# PWR2.net
KiCad netlist of a schematic drawn in Altium Designer
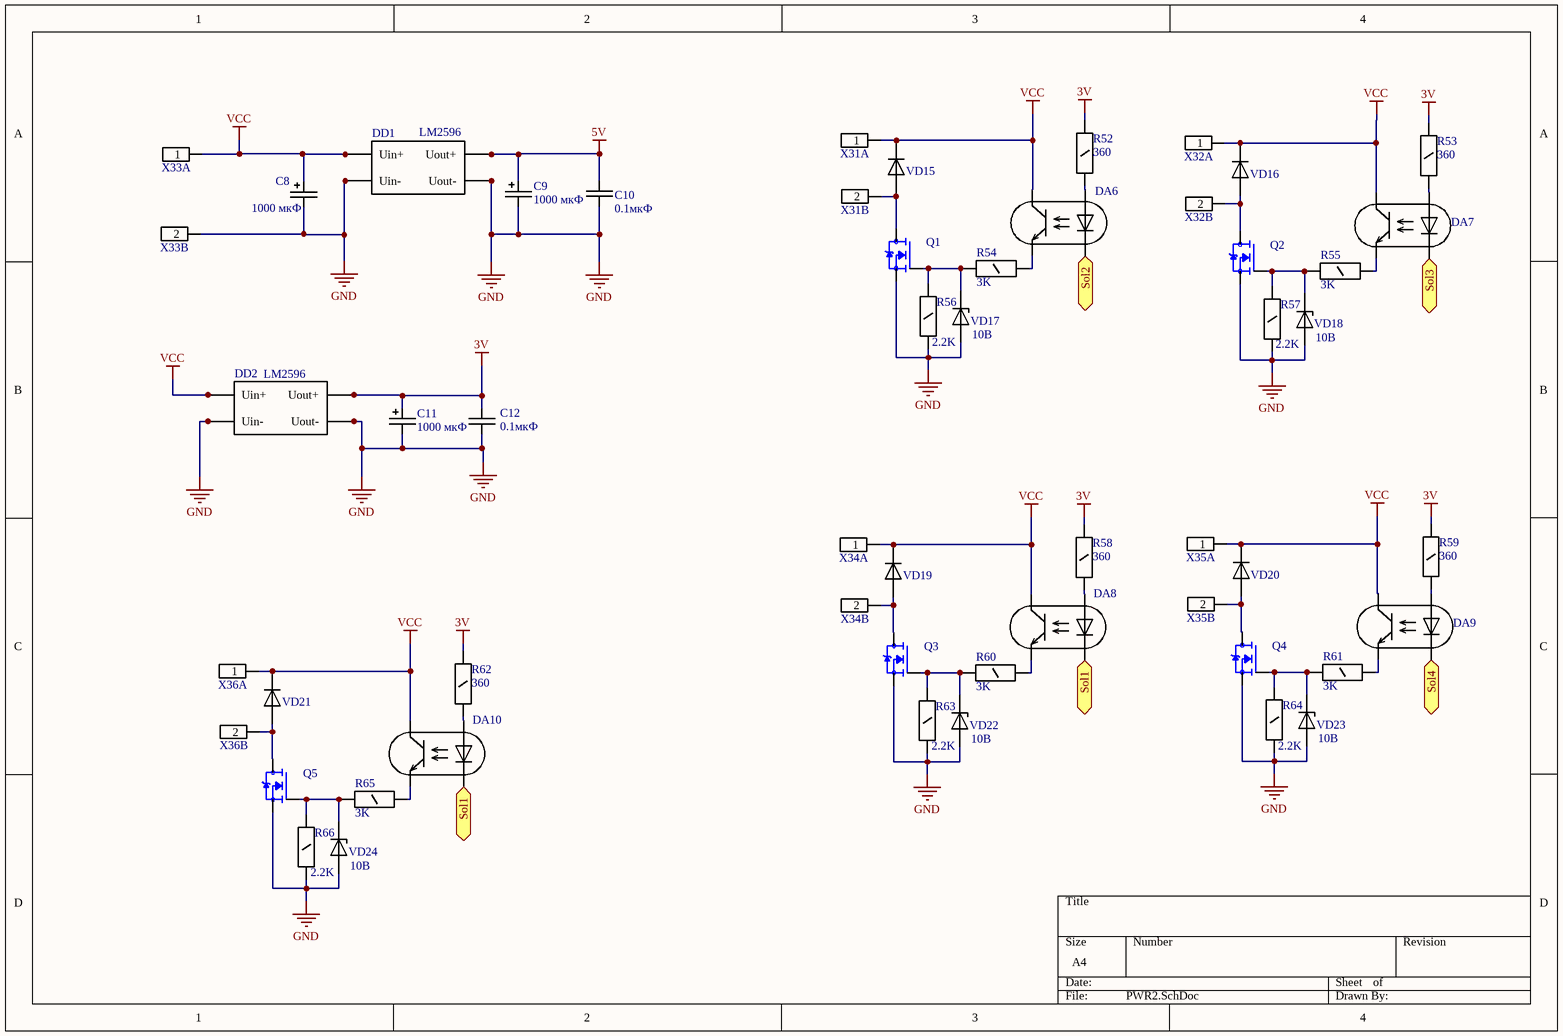
[diagram p0: PWR2.SchDoc]

(export (version "E")
  (design (tool "Eeschema 10.0.6"))
  (components
    (comp (ref "C8")
      (value "1000 мкФ")
      (footprint "C_10x5")
      (description "К50-35")
      (fields (field (name "TOLERANCE") "20%"))
      (libsource (lib "Res_end_Cap") (part "Конденсатор 25х12.5"))
    )
    (comp (ref "C9")
      (value "1000 мкФ")
      (footprint "C_10x5")
      (description "К50-35")
      (fields (field (name "TOLERANCE") "20%"))
      (libsource (lib "Res_end_Cap") (part "Конденсатор 25х12.5"))
    )
    (comp (ref "C10")
      (value "0.1мкФ")
      (footprint "C_1206")
      (description "SMD")
      (fields (field (name "VOLTAGE") "50B") (field (name "TOLERANCE") "10%"))
      (libsource (lib "Res_end_Cap") (part "Конденсатор 1210"))
    )
    (comp (ref "C11")
      (value "1000 мкФ")
      (footprint "C_10x5")
      (description "К50-35")
      (fields (field (name "TOLERANCE") "20%"))
      (libsource (lib "Res_end_Cap") (part "Конденсатор 25х12.5"))
    )
    (comp (ref "C12")
      (value "0.1мкФ")
      (footprint "C_1206")
      (description "SMD")
      (fields (field (name "VOLTAGE") "50B") (field (name "TOLERANCE") "10%"))
      (libsource (lib "Res_end_Cap") (part "Конденсатор 1210"))
    )
    (comp (ref "DA6")
      (value "KPC357NT0C")
      (footprint "Mini-flat-4")
      (description "оптрон, SMD")
      (libsource (lib "LEDendIND") (part "KPC357NT"))
    )
    (comp (ref "DA7")
      (value "KPC357NT0C")
      (footprint "Mini-flat-4")
      (description "оптрон, SMD")
      (libsource (lib "LEDendIND") (part "KPC357NT"))
    )
    (comp (ref "DA8")
      (value "KPC357NT0C")
      (footprint "Mini-flat-4")
      (description "оптрон, SMD")
      (libsource (lib "LEDendIND") (part "KPC357NT"))
    )
    (comp (ref "DA9")
      (value "KPC357NT0C")
      (footprint "Mini-flat-4")
      (description "оптрон, SMD")
      (libsource (lib "LEDendIND") (part "KPC357NT"))
    )
    (comp (ref "DA10")
      (value "KPC357NT0C")
      (footprint "Mini-flat-4")
      (description "оптрон, SMD")
      (libsource (lib "LEDendIND") (part "KPC357NT"))
    )
    (comp (ref "DD1")
      (value "LM2596")
      (footprint "LM2596")
      (description "Блок питания")
      (libsource (lib "MODULE") (part "LM2596"))
    )
    (comp (ref "DD2")
      (value "LM2596")
      (footprint "LM2596")
      (description "Блок питания")
      (libsource (lib "MODULE") (part "LM2596"))
    )
    (comp (ref "Q1")
      (value "IRFZ44N")
      (footprint "DPAK254P1524X483-3N:DPAK254P1524X483-3N")
      (description "N-Channel 55V 49A (Tc) 3.8W (Ta), 94W (Tc) Surface Mount D2PAK")
      (fields (field (name "MP") "IRFZ44NSTRRPBF") (field (name "MF") "Infineon Technologies"))
      (libsource (lib "Diod_transistor") (part "IRFZ44NSTRRPBF"))
    )
    (comp (ref "Q2")
      (value "IRFZ44N")
      (footprint "DPAK254P1524X483-3N:DPAK254P1524X483-3N")
      (description "N-Channel 55V 49A (Tc) 3.8W (Ta), 94W (Tc) Surface Mount D2PAK")
      (fields (field (name "MP") "IRFZ44NSTRRPBF") (field (name "MF") "Infineon Technologies"))
      (libsource (lib "Diod_transistor") (part "IRFZ44NSTRRPBF"))
    )
    (comp (ref "Q3")
      (value "IRFZ44N")
      (footprint "DPAK254P1524X483-3N:DPAK254P1524X483-3N")
      (description "N-Channel 55V 49A (Tc) 3.8W (Ta), 94W (Tc) Surface Mount D2PAK")
      (fields (field (name "MP") "IRFZ44NSTRRPBF") (field (name "MF") "Infineon Technologies"))
      (libsource (lib "Diod_transistor") (part "IRFZ44NSTRRPBF"))
    )
    (comp (ref "Q4")
      (value "IRFZ44N")
      (footprint "DPAK254P1524X483-3N:DPAK254P1524X483-3N")
      (description "N-Channel 55V 49A (Tc) 3.8W (Ta), 94W (Tc) Surface Mount D2PAK")
      (fields (field (name "MP") "IRFZ44NSTRRPBF") (field (name "MF") "Infineon Technologies"))
      (libsource (lib "Diod_transistor") (part "IRFZ44NSTRRPBF"))
    )
    (comp (ref "Q5")
      (value "IRFZ44N")
      (footprint "DPAK254P1524X483-3N:DPAK254P1524X483-3N")
      (description "N-Channel 55V 49A (Tc) 3.8W (Ta), 94W (Tc) Surface Mount D2PAK")
      (fields (field (name "MP") "IRFZ44NSTRRPBF") (field (name "MF") "Infineon Technologies"))
      (libsource (lib "Diod_transistor") (part "IRFZ44NSTRRPBF"))
    )
    (comp (ref "R52")
      (value "360")
      (footprint "R_1206")
      (description "0,25 Вт")
      (fields (field (name "POWER") "0.25 Вт") (field (name "TOLERANCE") "5%"))
      (libsource (lib "Res_end_Cap") (part "Резистор 1206"))
    )
    (comp (ref "R53")
      (value "360")
      (footprint "R_1206")
      (description "0,25 Вт")
      (fields (field (name "POWER") "0.25 Вт") (field (name "TOLERANCE") "5%"))
      (libsource (lib "Res_end_Cap") (part "Резистор 1206"))
    )
    (comp (ref "R54")
      (value "3K")
      (footprint "R_1206")
      (description "0,25 Вт")
      (fields (field (name "POWER") "0.25 Вт") (field (name "TOLERANCE") "5%"))
      (libsource (lib "") (part "Резистор 1206_2"))
    )
    (comp (ref "R55")
      (value "3K")
      (footprint "R_1206")
      (description "0,25 Вт")
      (fields (field (name "POWER") "0.25 Вт") (field (name "TOLERANCE") "5%"))
      (libsource (lib "") (part "Резистор 1206_2"))
    )
    (comp (ref "R56")
      (value "2.2K")
      (footprint "R_1206")
      (description "0,25 Вт")
      (fields (field (name "POWER") "0.25 Вт") (field (name "TOLERANCE") "5%"))
      (libsource (lib "") (part "Резистор 1206_1"))
    )
    (comp (ref "R57")
      (value "2.2K")
      (footprint "R_1206")
      (description "0,25 Вт")
      (fields (field (name "POWER") "0.25 Вт") (field (name "TOLERANCE") "5%"))
      (libsource (lib "") (part "Резистор 1206_1"))
    )
    (comp (ref "R58")
      (value "360")
      (footprint "R_1206")
      (description "0,25 Вт")
      (fields (field (name "POWER") "0.25 Вт") (field (name "TOLERANCE") "5%"))
      (libsource (lib "Res_end_Cap") (part "Резистор 1206"))
    )
    (comp (ref "R59")
      (value "360")
      (footprint "R_1206")
      (description "0,25 Вт")
      (fields (field (name "POWER") "0.25 Вт") (field (name "TOLERANCE") "5%"))
      (libsource (lib "Res_end_Cap") (part "Резистор 1206"))
    )
    (comp (ref "R60")
      (value "3K")
      (footprint "R_1206")
      (description "0,25 Вт")
      (fields (field (name "POWER") "0.25 Вт") (field (name "TOLERANCE") "5%"))
      (libsource (lib "") (part "Резистор 1206_2"))
    )
    (comp (ref "R61")
      (value "3K")
      (footprint "R_1206")
      (description "0,25 Вт")
      (fields (field (name "POWER") "0.25 Вт") (field (name "TOLERANCE") "5%"))
      (libsource (lib "") (part "Резистор 1206_2"))
    )
    (comp (ref "R62")
      (value "360")
      (footprint "R_1206")
      (description "0,25 Вт")
      (fields (field (name "POWER") "0.25 Вт") (field (name "TOLERANCE") "5%"))
      (libsource (lib "Res_end_Cap") (part "Резистор 1206"))
    )
    (comp (ref "R63")
      (value "2.2K")
      (footprint "R_1206")
      (description "0,25 Вт")
      (fields (field (name "POWER") "0.25 Вт") (field (name "TOLERANCE") "5%"))
      (libsource (lib "") (part "Резистор 1206_1"))
    )
    (comp (ref "R64")
      (value "2.2K")
      (footprint "R_1206")
      (description "0,25 Вт")
      (fields (field (name "POWER") "0.25 Вт") (field (name "TOLERANCE") "5%"))
      (libsource (lib "") (part "Резистор 1206_1"))
    )
    (comp (ref "R65")
      (value "3K")
      (footprint "R_1206")
      (description "0,25 Вт")
      (fields (field (name "POWER") "0.25 Вт") (field (name "TOLERANCE") "5%"))
      (libsource (lib "") (part "Резистор 1206_2"))
    )
    (comp (ref "R66")
      (value "2.2K")
      (footprint "R_1206")
      (description "0,25 Вт")
      (fields (field (name "POWER") "0.25 Вт") (field (name "TOLERANCE") "5%"))
      (libsource (lib "") (part "Резистор 1206_1"))
    )
    (comp (ref "VD15")
      (value "SMA400*")
      (footprint "SMA (DO-214AC)")
      (description "диод, SMD")
      (libsource (lib "Диоды и транзисторы") (part "SMA400*"))
    )
    (comp (ref "VD16")
      (value "SMA400*")
      (footprint "SMA (DO-214AC)")
      (description "диод, SMD")
      (libsource (lib "Диоды и транзисторы") (part "SMA400*"))
    )
    (comp (ref "VD17")
      (value "10В")
      (footprint "DL-35")
      (description "стабилитрон, SMD")
      (fields (field (name "POWER") "0.5 Вт"))
      (libsource (lib "Diod_transistor") (part "BZV55C***"))
    )
    (comp (ref "VD18")
      (value "10В")
      (footprint "DL-35")
      (description "стабилитрон, SMD")
      (fields (field (name "POWER") "0.5 Вт"))
      (libsource (lib "Diod_transistor") (part "BZV55C***"))
    )
    (comp (ref "VD19")
      (value "SMA400*")
      (footprint "SMA (DO-214AC)")
      (description "диод, SMD")
      (libsource (lib "Диоды и транзисторы") (part "SMA400*"))
    )
    (comp (ref "VD20")
      (value "SMA400*")
      (footprint "SMA (DO-214AC)")
      (description "диод, SMD")
      (libsource (lib "Диоды и транзисторы") (part "SMA400*"))
    )
    (comp (ref "VD21")
      (value "SMA400*")
      (footprint "SMA (DO-214AC)")
      (description "диод, SMD")
      (libsource (lib "Диоды и транзисторы") (part "SMA400*"))
    )
    (comp (ref "VD22")
      (value "10В")
      (footprint "DL-35")
      (description "стабилитрон, SMD")
      (fields (field (name "POWER") "0.5 Вт"))
      (libsource (lib "Diod_transistor") (part "BZV55C***"))
    )
    (comp (ref "VD23")
      (value "10В")
      (footprint "DL-35")
      (description "стабилитрон, SMD")
      (fields (field (name "POWER") "0.5 Вт"))
      (libsource (lib "Diod_transistor") (part "BZV55C***"))
    )
    (comp (ref "VD24")
      (value "10В")
      (footprint "DL-35")
      (description "стабилитрон, SMD")
      (fields (field (name "POWER") "0.5 Вт"))
      (libsource (lib "Diod_transistor") (part "BZV55C***"))
    )
    (comp (ref "X31")
      (value "DG508V-02")
      (footprint "DG508V-02")
      (description "клеммник винтовой 2к.,5.08мм")
      (libsource (lib "Klemniki") (part "DG508V-02"))
    )
    (comp (ref "X32")
      (value "DG508V-02")
      (footprint "DG508V-02")
      (description "клеммник винтовой 2к.,5.08мм")
      (libsource (lib "Klemniki") (part "DG508V-02"))
    )
    (comp (ref "X33")
      (value "DG508V-02")
      (footprint "DG508V-02")
      (description "клеммник винтовой 2к.,5.08мм")
      (libsource (lib "Klemniki") (part "DG508V-02"))
    )
    (comp (ref "X34")
      (value "DG508V-02")
      (footprint "DG508V-02")
      (description "клеммник винтовой 2к.,5.08мм")
      (libsource (lib "Klemniki") (part "DG508V-02"))
    )
    (comp (ref "X35")
      (value "DG508V-02")
      (footprint "DG508V-02")
      (description "клеммник винтовой 2к.,5.08мм")
      (libsource (lib "Klemniki") (part "DG508V-02"))
    )
    (comp (ref "X36")
      (value "DG508V-02")
      (footprint "DG508V-02")
      (description "клеммник винтовой 2к.,5.08мм")
      (libsource (lib "Klemniki") (part "DG508V-02"))
    )
  )
  (nets
    (net (code "1") (name "/Sol1") (class "Default")
      (node (ref "DA10") (pin "2") (pinfunction "2_2") (pintype "passive"))
      (node (ref "DA8") (pin "2") (pinfunction "2_2") (pintype "passive"))
    )
    (net (code "2") (name "/Sol2") (class "Default")
      (node (ref "DA6") (pin "2") (pinfunction "2_2") (pintype "passive"))
    )
    (net (code "3") (name "/Sol3") (class "Default")
      (node (ref "DA7") (pin "2") (pinfunction "2_2") (pintype "passive"))
    )
    (net (code "4") (name "/Sol4") (class "Default")
      (node (ref "DA9") (pin "2") (pinfunction "2_2") (pintype "passive"))
    )
    (net (code "5") (name "3V") (class "Default")
      (node (ref "C11") (pin "1") (pinfunction "1_1") (pintype "passive"))
      (node (ref "C12") (pin "1") (pinfunction "1_1") (pintype "passive"))
      (node (ref "DD2") (pin "5") (pinfunction "Uout+_5") (pintype "power_in"))
      (node (ref "DD2") (pin "6") (pinfunction "Uout+_6") (pintype "power_in"))
      (node (ref "R52") (pin "1") (pinfunction "1_1") (pintype "passive"))
      (node (ref "R53") (pin "1") (pinfunction "1_1") (pintype "passive"))
      (node (ref "R58") (pin "1") (pinfunction "1_1") (pintype "passive"))
      (node (ref "R59") (pin "1") (pinfunction "1_1") (pintype "passive"))
      (node (ref "R62") (pin "1") (pinfunction "1_1") (pintype "passive"))
    )
    (net (code "6") (name "5V") (class "Default")
      (node (ref "C10") (pin "1") (pinfunction "1_1") (pintype "passive"))
      (node (ref "C9") (pin "1") (pinfunction "1_1") (pintype "passive"))
      (node (ref "DD1") (pin "5") (pinfunction "Uout+_5") (pintype "power_in"))
      (node (ref "DD1") (pin "6") (pinfunction "Uout+_6") (pintype "power_in"))
    )
    (net (code "7") (name "GND") (class "Default")
      (node (ref "C10") (pin "2") (pinfunction "2_2") (pintype "passive"))
      (node (ref "C11") (pin "2") (pinfunction "2_2") (pintype "passive"))
      (node (ref "C12") (pin "2") (pinfunction "2_2") (pintype "passive"))
      (node (ref "C8") (pin "2") (pinfunction "2_2") (pintype "passive"))
      (node (ref "C9") (pin "2") (pinfunction "2_2") (pintype "passive"))
      (node (ref "DD1") (pin "3") (pinfunction "Uin-_3") (pintype "power_in"))
      (node (ref "DD1") (pin "4") (pinfunction "Uin-_4") (pintype "power_in"))
      (node (ref "DD1") (pin "7") (pinfunction "Uout-_7") (pintype "power_in"))
      (node (ref "DD1") (pin "8") (pinfunction "Uout-_8") (pintype "power_in"))
      (node (ref "DD2") (pin "3") (pinfunction "Uin-_3") (pintype "power_in"))
      (node (ref "DD2") (pin "4") (pinfunction "Uin-_4") (pintype "power_in"))
      (node (ref "DD2") (pin "7") (pinfunction "Uout-_7") (pintype "power_in"))
      (node (ref "DD2") (pin "8") (pinfunction "Uout-_8") (pintype "power_in"))
      (node (ref "Q1") (pin "3") (pinfunction "S_3") (pintype "passive"))
      (node (ref "Q2") (pin "3") (pinfunction "S_3") (pintype "passive"))
      (node (ref "Q3") (pin "3") (pinfunction "S_3") (pintype "passive"))
      (node (ref "Q4") (pin "3") (pinfunction "S_3") (pintype "passive"))
      (node (ref "Q5") (pin "3") (pinfunction "S_3") (pintype "passive"))
      (node (ref "R56") (pin "1") (pinfunction "1_1") (pintype "passive"))
      (node (ref "R57") (pin "1") (pinfunction "1_1") (pintype "passive"))
      (node (ref "R63") (pin "1") (pinfunction "1_1") (pintype "passive"))
      (node (ref "R64") (pin "1") (pinfunction "1_1") (pintype "passive"))
      (node (ref "R66") (pin "1") (pinfunction "1_1") (pintype "passive"))
      (node (ref "VD17") (pin "1") (pinfunction "1_1") (pintype "passive"))
      (node (ref "VD18") (pin "1") (pinfunction "1_1") (pintype "passive"))
      (node (ref "VD22") (pin "1") (pinfunction "1_1") (pintype "passive"))
      (node (ref "VD23") (pin "1") (pinfunction "1_1") (pintype "passive"))
      (node (ref "VD24") (pin "1") (pinfunction "1_1") (pintype "passive"))
      (node (ref "X33") (pin "2") (pinfunction "2_2") (pintype "passive"))
    )
    (net (code "8") (name "Net-(DA6-Pad1)") (class "Default")
      (node (ref "DA6") (pin "1") (pinfunction "1_1") (pintype "passive"))
      (node (ref "R52") (pin "2") (pinfunction "2_2") (pintype "passive"))
    )
    (net (code "9") (name "Net-(DA6-Pad3)") (class "Default")
      (node (ref "DA6") (pin "3") (pinfunction "3_3") (pintype "passive"))
      (node (ref "R54") (pin "2") (pinfunction "2_2") (pintype "passive"))
    )
    (net (code "10") (name "Net-(DA7-Pad1)") (class "Default")
      (node (ref "DA7") (pin "1") (pinfunction "1_1") (pintype "passive"))
      (node (ref "R53") (pin "2") (pinfunction "2_2") (pintype "passive"))
    )
    (net (code "11") (name "Net-(DA7-Pad3)") (class "Default")
      (node (ref "DA7") (pin "3") (pinfunction "3_3") (pintype "passive"))
      (node (ref "R55") (pin "2") (pinfunction "2_2") (pintype "passive"))
    )
    (net (code "12") (name "Net-(DA8-Pad1)") (class "Default")
      (node (ref "DA8") (pin "1") (pinfunction "1_1") (pintype "passive"))
      (node (ref "R58") (pin "2") (pinfunction "2_2") (pintype "passive"))
    )
    (net (code "13") (name "Net-(DA8-Pad3)") (class "Default")
      (node (ref "DA8") (pin "3") (pinfunction "3_3") (pintype "passive"))
      (node (ref "R60") (pin "2") (pinfunction "2_2") (pintype "passive"))
    )
    (net (code "14") (name "Net-(DA9-Pad1)") (class "Default")
      (node (ref "DA9") (pin "1") (pinfunction "1_1") (pintype "passive"))
      (node (ref "R59") (pin "2") (pinfunction "2_2") (pintype "passive"))
    )
    (net (code "15") (name "Net-(DA9-Pad3)") (class "Default")
      (node (ref "DA9") (pin "3") (pinfunction "3_3") (pintype "passive"))
      (node (ref "R61") (pin "2") (pinfunction "2_2") (pintype "passive"))
    )
    (net (code "16") (name "Net-(DA10-Pad1)") (class "Default")
      (node (ref "DA10") (pin "1") (pinfunction "1_1") (pintype "passive"))
      (node (ref "R62") (pin "2") (pinfunction "2_2") (pintype "passive"))
    )
    (net (code "17") (name "Net-(DA10-Pad3)") (class "Default")
      (node (ref "DA10") (pin "3") (pinfunction "3_3") (pintype "passive"))
      (node (ref "R65") (pin "2") (pinfunction "2_2") (pintype "passive"))
    )
    (net (code "18") (name "Net-(Q1-D)") (class "Default")
      (node (ref "Q1") (pin "2") (pinfunction "D_2") (pintype "passive"))
      (node (ref "VD15") (pin "A") (pinfunction "A_A") (pintype "passive"))
      (node (ref "X31") (pin "2") (pinfunction "2_2") (pintype "passive"))
    )
    (net (code "19") (name "Net-(Q1-G)") (class "Default")
      (node (ref "Q1") (pin "1") (pinfunction "G_1") (pintype "passive"))
      (node (ref "R54") (pin "1") (pinfunction "1_1") (pintype "passive"))
      (node (ref "R56") (pin "2") (pinfunction "2_2") (pintype "passive"))
      (node (ref "VD17") (pin "2") (pinfunction "2_2") (pintype "passive"))
    )
    (net (code "20") (name "Net-(Q2-D)") (class "Default")
      (node (ref "Q2") (pin "2") (pinfunction "D_2") (pintype "passive"))
      (node (ref "VD16") (pin "A") (pinfunction "A_A") (pintype "passive"))
      (node (ref "X32") (pin "2") (pinfunction "2_2") (pintype "passive"))
    )
    (net (code "21") (name "Net-(Q2-G)") (class "Default")
      (node (ref "Q2") (pin "1") (pinfunction "G_1") (pintype "passive"))
      (node (ref "R55") (pin "1") (pinfunction "1_1") (pintype "passive"))
      (node (ref "R57") (pin "2") (pinfunction "2_2") (pintype "passive"))
      (node (ref "VD18") (pin "2") (pinfunction "2_2") (pintype "passive"))
    )
    (net (code "22") (name "Net-(Q3-D)") (class "Default")
      (node (ref "Q3") (pin "2") (pinfunction "D_2") (pintype "passive"))
      (node (ref "VD19") (pin "A") (pinfunction "A_A") (pintype "passive"))
      (node (ref "X34") (pin "2") (pinfunction "2_2") (pintype "passive"))
    )
    (net (code "23") (name "Net-(Q3-G)") (class "Default")
      (node (ref "Q3") (pin "1") (pinfunction "G_1") (pintype "passive"))
      (node (ref "R60") (pin "1") (pinfunction "1_1") (pintype "passive"))
      (node (ref "R63") (pin "2") (pinfunction "2_2") (pintype "passive"))
      (node (ref "VD22") (pin "2") (pinfunction "2_2") (pintype "passive"))
    )
    (net (code "24") (name "Net-(Q4-D)") (class "Default")
      (node (ref "Q4") (pin "2") (pinfunction "D_2") (pintype "passive"))
      (node (ref "VD20") (pin "A") (pinfunction "A_A") (pintype "passive"))
      (node (ref "X35") (pin "2") (pinfunction "2_2") (pintype "passive"))
    )
    (net (code "25") (name "Net-(Q4-G)") (class "Default")
      (node (ref "Q4") (pin "1") (pinfunction "G_1") (pintype "passive"))
      (node (ref "R61") (pin "1") (pinfunction "1_1") (pintype "passive"))
      (node (ref "R64") (pin "2") (pinfunction "2_2") (pintype "passive"))
      (node (ref "VD23") (pin "2") (pinfunction "2_2") (pintype "passive"))
    )
    (net (code "26") (name "Net-(Q5-D)") (class "Default")
      (node (ref "Q5") (pin "2") (pinfunction "D_2") (pintype "passive"))
      (node (ref "VD21") (pin "A") (pinfunction "A_A") (pintype "passive"))
      (node (ref "X36") (pin "2") (pinfunction "2_2") (pintype "passive"))
    )
    (net (code "27") (name "Net-(Q5-G)") (class "Default")
      (node (ref "Q5") (pin "1") (pinfunction "G_1") (pintype "passive"))
      (node (ref "R65") (pin "1") (pinfunction "1_1") (pintype "passive"))
      (node (ref "R66") (pin "2") (pinfunction "2_2") (pintype "passive"))
      (node (ref "VD24") (pin "2") (pinfunction "2_2") (pintype "passive"))
    )
    (net (code "28") (name "VCC") (class "Default")
      (node (ref "C8") (pin "1") (pinfunction "1_1") (pintype "passive"))
      (node (ref "DA10") (pin "4") (pinfunction "4_4") (pintype "passive"))
      (node (ref "DA6") (pin "4") (pinfunction "4_4") (pintype "passive"))
      (node (ref "DA7") (pin "4") (pinfunction "4_4") (pintype "passive"))
      (node (ref "DA8") (pin "4") (pinfunction "4_4") (pintype "passive"))
      (node (ref "DA9") (pin "4") (pinfunction "4_4") (pintype "passive"))
      (node (ref "DD1") (pin "1") (pinfunction "Uin+_1") (pintype "power_in"))
      (node (ref "DD1") (pin "2") (pinfunction "Uin+_2") (pintype "power_in"))
      (node (ref "DD2") (pin "1") (pinfunction "Uin+_1") (pintype "power_in"))
      (node (ref "DD2") (pin "2") (pinfunction "Uin+_2") (pintype "power_in"))
      (node (ref "VD15") (pin "K") (pinfunction "K_K") (pintype "passive"))
      (node (ref "VD16") (pin "K") (pinfunction "K_K") (pintype "passive"))
      (node (ref "VD19") (pin "K") (pinfunction "K_K") (pintype "passive"))
      (node (ref "VD20") (pin "K") (pinfunction "K_K") (pintype "passive"))
      (node (ref "VD21") (pin "K") (pinfunction "K_K") (pintype "passive"))
      (node (ref "X31") (pin "1") (pinfunction "1_1") (pintype "passive"))
      (node (ref "X32") (pin "1") (pinfunction "1_1") (pintype "passive"))
      (node (ref "X33") (pin "1") (pinfunction "1_1") (pintype "passive"))
      (node (ref "X34") (pin "1") (pinfunction "1_1") (pintype "passive"))
      (node (ref "X35") (pin "1") (pinfunction "1_1") (pintype "passive"))
      (node (ref "X36") (pin "1") (pinfunction "1_1") (pintype "passive"))
    )
  )
)
